# IMUAndSonar.net
KiCad netlist of a schematic drawn in Altium Designer
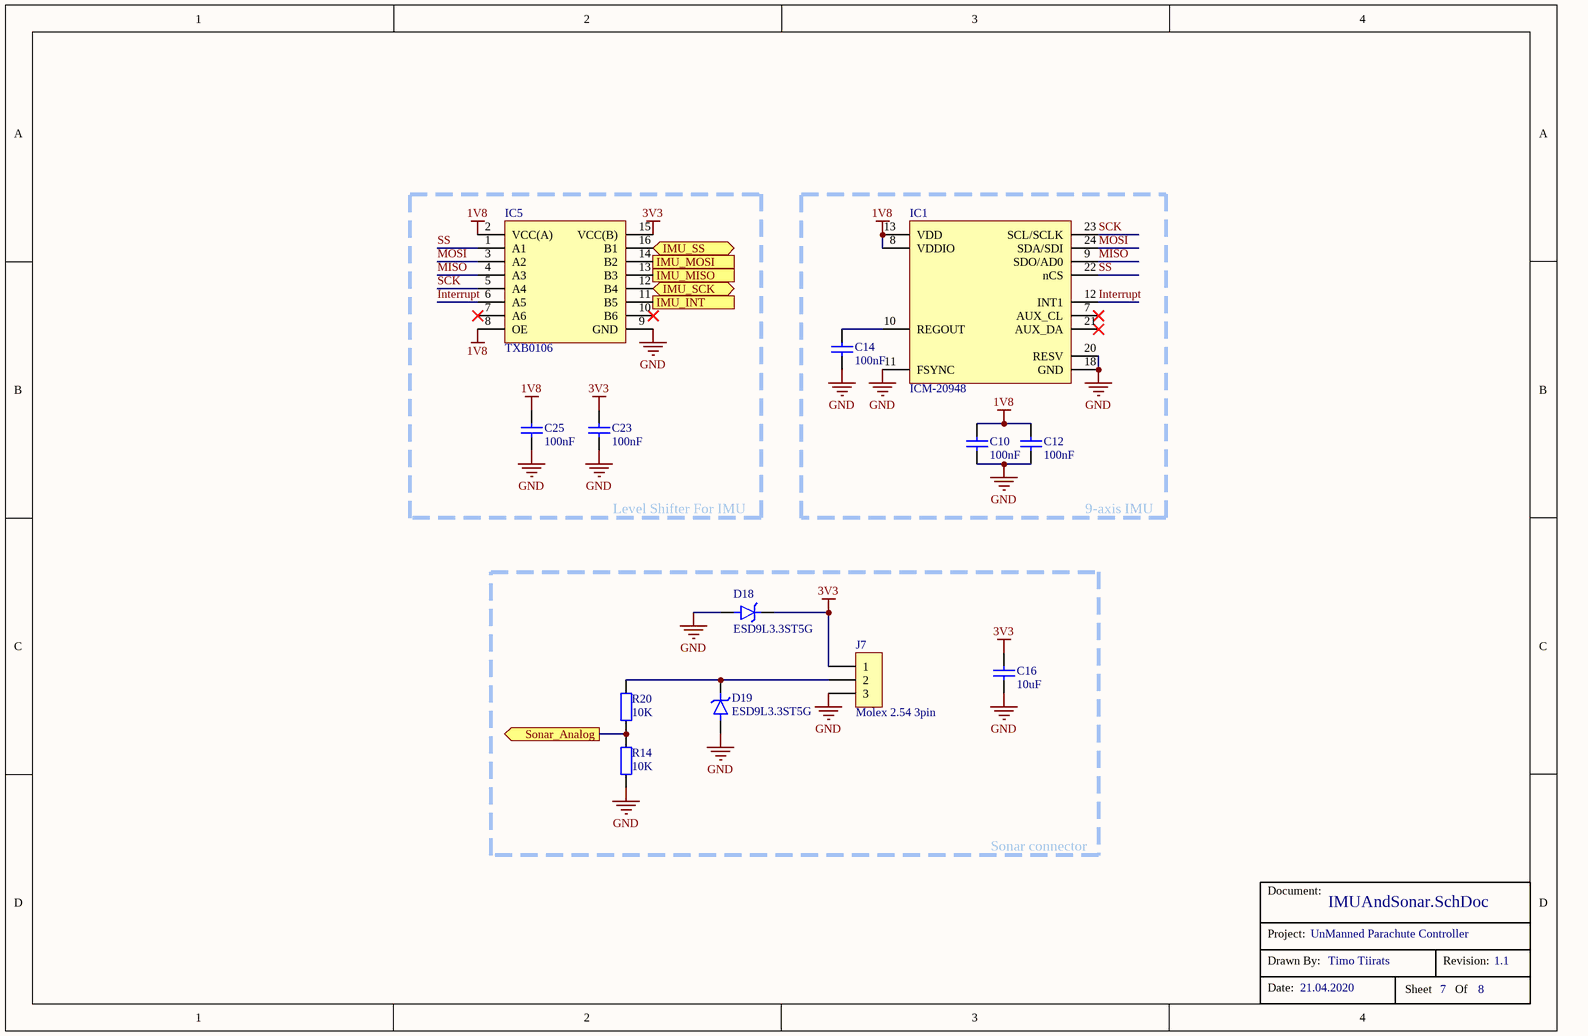
[diagram p0: IMUAndSonar.SchDoc]

(export (version "E")
  (design (tool "Eeschema 10.0.6"))
  (components
    (comp (ref "C10")
      (value "100nF*V")
      (footprint "C0603 N")
      (description "Ceramic capacitor")
      (fields (field (name "CAPACITANCE") "100nF"))
      (libsource (lib "Passives") (part "Capacitor"))
    )
    (comp (ref "C12")
      (value "100nF*V")
      (footprint "C0603 N")
      (description "Ceramic capacitor")
      (fields (field (name "CAPACITANCE") "100nF"))
      (libsource (lib "Passives") (part "Capacitor"))
    )
    (comp (ref "C14")
      (value "100nF*V")
      (footprint "C0603 N")
      (description "Ceramic capacitor")
      (fields (field (name "CAPACITANCE") "100nF"))
      (libsource (lib "Passives") (part "Capacitor"))
    )
    (comp (ref "C16")
      (value "10uF*V")
      (footprint "C1206 N")
      (description "Ceramic capacitor")
      (fields (field (name "CAPACITANCE") "10uF"))
      (libsource (lib "Passives") (part "Capacitor"))
    )
    (comp (ref "C23")
      (value "100nF*V")
      (footprint "C0603 N")
      (description "Ceramic capacitor")
      (fields (field (name "CAPACITANCE") "100nF"))
      (libsource (lib "Passives") (part "Capacitor"))
    )
    (comp (ref "C25")
      (value "100nF*V")
      (footprint "C0603 N")
      (description "Ceramic capacitor")
      (fields (field (name "CAPACITANCE") "100nF"))
      (libsource (lib "Passives") (part "Capacitor"))
    )
    (comp (ref "D18")
      (value "ESD9L3.3ST5G")
      (footprint "SOD923F, NOMINAL")
      (description "TVS DIODE, Unidir, 3.3V/9V, 150mW, SOD-923, ESD9L3.3ST5G, ON SEMICONDUCTOR")
      (fields (field (name "MANUFACTURER") "ON Semiconductor"))
      (libsource (lib "Diodes") (part "ESD9L3.3ST5G"))
    )
    (comp (ref "D19")
      (value "ESD9L3.3ST5G")
      (footprint "SOD923F, NOMINAL")
      (description "TVS DIODE, Unidir, 3.3V/9V, 150mW, SOD-923, ESD9L3.3ST5G, ON SEMICONDUCTOR")
      (fields (field (name "MANUFACTURER") "ON Semiconductor"))
      (libsource (lib "Diodes") (part "ESD9L3.3ST5G"))
    )
    (comp (ref "IC1")
      (value "ICM-20948")
      (footprint "QFN-24, 3x3MM, NOMINAL")
      (description "9-axis IMU, SPI and I2C, 1.8Vin, 24QFN")
      (libsource (lib "IMUs") (part "ICM-20948"))
    )
    (comp (ref "IC5")
      (value "TXB0106")
      (footprint "VQFN-16, 4x3.5MM, NOMINAL")
      (description "Level shifter, 6 inputs, 1.2 .. 5.5Vin, 4ns delay, TXB0106, TEXAS INSTRUMENTS")
      (libsource (lib "LevelShifters") (part "TXB0106"))
    )
    (comp (ref "J7")
      (value "Molex 2.54 3pin")
      (footprint "22-27-2031")
      (description "Molex header, 3 pin, KK 6410 series")
      (fields (field (name "MANUFACTURER PART NUMBER") "22-27-2031"))
      (libsource (lib "molex_kk") (part "Molex header, 3 pin, KK 6410 series"))
    )
    (comp (ref "R14")
      (value "10K")
      (footprint "R0603")
      (description "Resistor")
      (fields (field (name "RESISTANCE") "10K"))
      (libsource (lib "") (part "Resistor_1"))
    )
    (comp (ref "R20")
      (value "10K")
      (footprint "R0603")
      (description "Resistor")
      (fields (field (name "RESISTANCE") "10K"))
      (libsource (lib "Passives") (part "Resistor"))
    )
  )
  (nets
    (net (code "1") (name "/IMU_INT") (class "Default")
      (node (ref "IC5") (pin "11") (pinfunction "B5_11") (pintype "passive"))
    )
    (net (code "2") (name "/IMU_MISO") (class "Default")
      (node (ref "IC5") (pin "13") (pinfunction "B3_13") (pintype "passive"))
    )
    (net (code "3") (name "/IMU_MOSI") (class "Default")
      (node (ref "IC5") (pin "14") (pinfunction "B2_14") (pintype "passive"))
    )
    (net (code "4") (name "/IMU_SCK") (class "Default")
      (node (ref "IC5") (pin "12") (pinfunction "B4_12") (pintype "passive"))
    )
    (net (code "5") (name "/IMU_SS") (class "Default")
      (node (ref "IC5") (pin "16") (pinfunction "B1_16") (pintype "passive"))
    )
    (net (code "6") (name "/Interrupt") (class "Default")
      (node (ref "IC1") (pin "12") (pinfunction "INT1_12") (pintype "passive"))
      (node (ref "IC5") (pin "6") (pinfunction "A5_6") (pintype "passive"))
    )
    (net (code "7") (name "/MISO") (class "Default")
      (node (ref "IC1") (pin "9") (pinfunction "SDO/AD0_9") (pintype "passive"))
      (node (ref "IC5") (pin "4") (pinfunction "A3_4") (pintype "passive"))
    )
    (net (code "8") (name "/MOSI") (class "Default")
      (node (ref "IC1") (pin "24") (pinfunction "SDA/SDI_24") (pintype "passive"))
      (node (ref "IC5") (pin "3") (pinfunction "A2_3") (pintype "passive"))
    )
    (net (code "9") (name "/SCK") (class "Default")
      (node (ref "IC1") (pin "23") (pinfunction "SCL/SCLK_23") (pintype "passive"))
      (node (ref "IC5") (pin "5") (pinfunction "A4_5") (pintype "passive"))
    )
    (net (code "10") (name "/SS") (class "Default")
      (node (ref "IC1") (pin "22") (pinfunction "nCS_22") (pintype "passive"))
      (node (ref "IC5") (pin "1") (pinfunction "A1_1") (pintype "passive"))
    )
    (net (code "11") (name "/Sonar_Analog") (class "Default")
      (node (ref "R14") (pin "1") (pinfunction "1_1") (pintype "passive"))
      (node (ref "R20") (pin "2") (pinfunction "2_2") (pintype "passive"))
    )
    (net (code "12") (name "1V8") (class "Default")
      (node (ref "C10") (pin "2") (pinfunction "2_2") (pintype "passive"))
      (node (ref "C12") (pin "2") (pinfunction "2_2") (pintype "passive"))
      (node (ref "C25") (pin "2") (pinfunction "2_2") (pintype "passive"))
      (node (ref "IC1") (pin "13") (pinfunction "VDD_13") (pintype "passive"))
      (node (ref "IC1") (pin "8") (pinfunction "VDDIO_8") (pintype "passive"))
      (node (ref "IC5") (pin "2") (pinfunction "VCC(A)_2") (pintype "passive"))
      (node (ref "IC5") (pin "8") (pinfunction "OE_8") (pintype "passive"))
    )
    (net (code "13") (name "3V3") (class "Default")
      (node (ref "C16") (pin "2") (pinfunction "2_2") (pintype "passive"))
      (node (ref "C23") (pin "2") (pinfunction "2_2") (pintype "passive"))
      (node (ref "D18") (pin "C") (pinfunction "C_C") (pintype "passive"))
      (node (ref "IC5") (pin "15") (pinfunction "VCC(B)_15") (pintype "passive"))
      (node (ref "J7") (pin "1") (pinfunction "1_1") (pintype "passive"))
    )
    (net (code "14") (name "GND") (class "Default")
      (node (ref "C10") (pin "1") (pinfunction "1_1") (pintype "passive"))
      (node (ref "C12") (pin "1") (pinfunction "1_1") (pintype "passive"))
      (node (ref "C14") (pin "1") (pinfunction "1_1") (pintype "passive"))
      (node (ref "C16") (pin "1") (pinfunction "1_1") (pintype "passive"))
      (node (ref "C23") (pin "1") (pinfunction "1_1") (pintype "passive"))
      (node (ref "C25") (pin "1") (pinfunction "1_1") (pintype "passive"))
      (node (ref "D18") (pin "A") (pinfunction "A_A") (pintype "passive"))
      (node (ref "D19") (pin "A") (pinfunction "A_A") (pintype "passive"))
      (node (ref "IC1") (pin "11") (pinfunction "FSYNC_11") (pintype "passive"))
      (node (ref "IC1") (pin "18") (pinfunction "GND_18") (pintype "passive"))
      (node (ref "IC1") (pin "20") (pinfunction "RESV_20") (pintype "passive"))
      (node (ref "IC5") (pin "9") (pinfunction "GND_9") (pintype "passive"))
      (node (ref "J7") (pin "3") (pinfunction "3_3") (pintype "passive"))
      (node (ref "R14") (pin "2") (pinfunction "2_2") (pintype "passive"))
    )
    (net (code "15") (name "Net-(D19-PadC)") (class "Default")
      (node (ref "D19") (pin "C") (pinfunction "C_C") (pintype "passive"))
      (node (ref "J7") (pin "2") (pinfunction "2_2") (pintype "passive"))
      (node (ref "R20") (pin "1") (pinfunction "1_1") (pintype "passive"))
    )
    (net (code "16") (name "Net-(IC1-REGOUT)") (class "Default")
      (node (ref "C14") (pin "2") (pinfunction "2_2") (pintype "passive"))
      (node (ref "IC1") (pin "10") (pinfunction "REGOUT_10") (pintype "passive"))
    )
    (net (code "17") (name "unconnected-(IC1-AUX_CL-Pad7)") (class "Default")
      (node (ref "IC1") (pin "7") (pinfunction "AUX_CL_7") (pintype "passive+no_connect"))
    )
    (net (code "18") (name "unconnected-(IC1-AUX_DA-Pad21)") (class "Default")
      (node (ref "IC1") (pin "21") (pinfunction "AUX_DA_21") (pintype "passive+no_connect"))
    )
    (net (code "19") (name "unconnected-(IC5-A6-Pad7)") (class "Default")
      (node (ref "IC5") (pin "7") (pinfunction "A6_7") (pintype "passive+no_connect"))
    )
    (net (code "20") (name "unconnected-(IC5-B6-Pad10)") (class "Default")
      (node (ref "IC5") (pin "10") (pinfunction "B6_10") (pintype "passive+no_connect"))
    )
  )
)
